# ESP32.net
KiCad netlist of a schematic drawn in Altium Designer
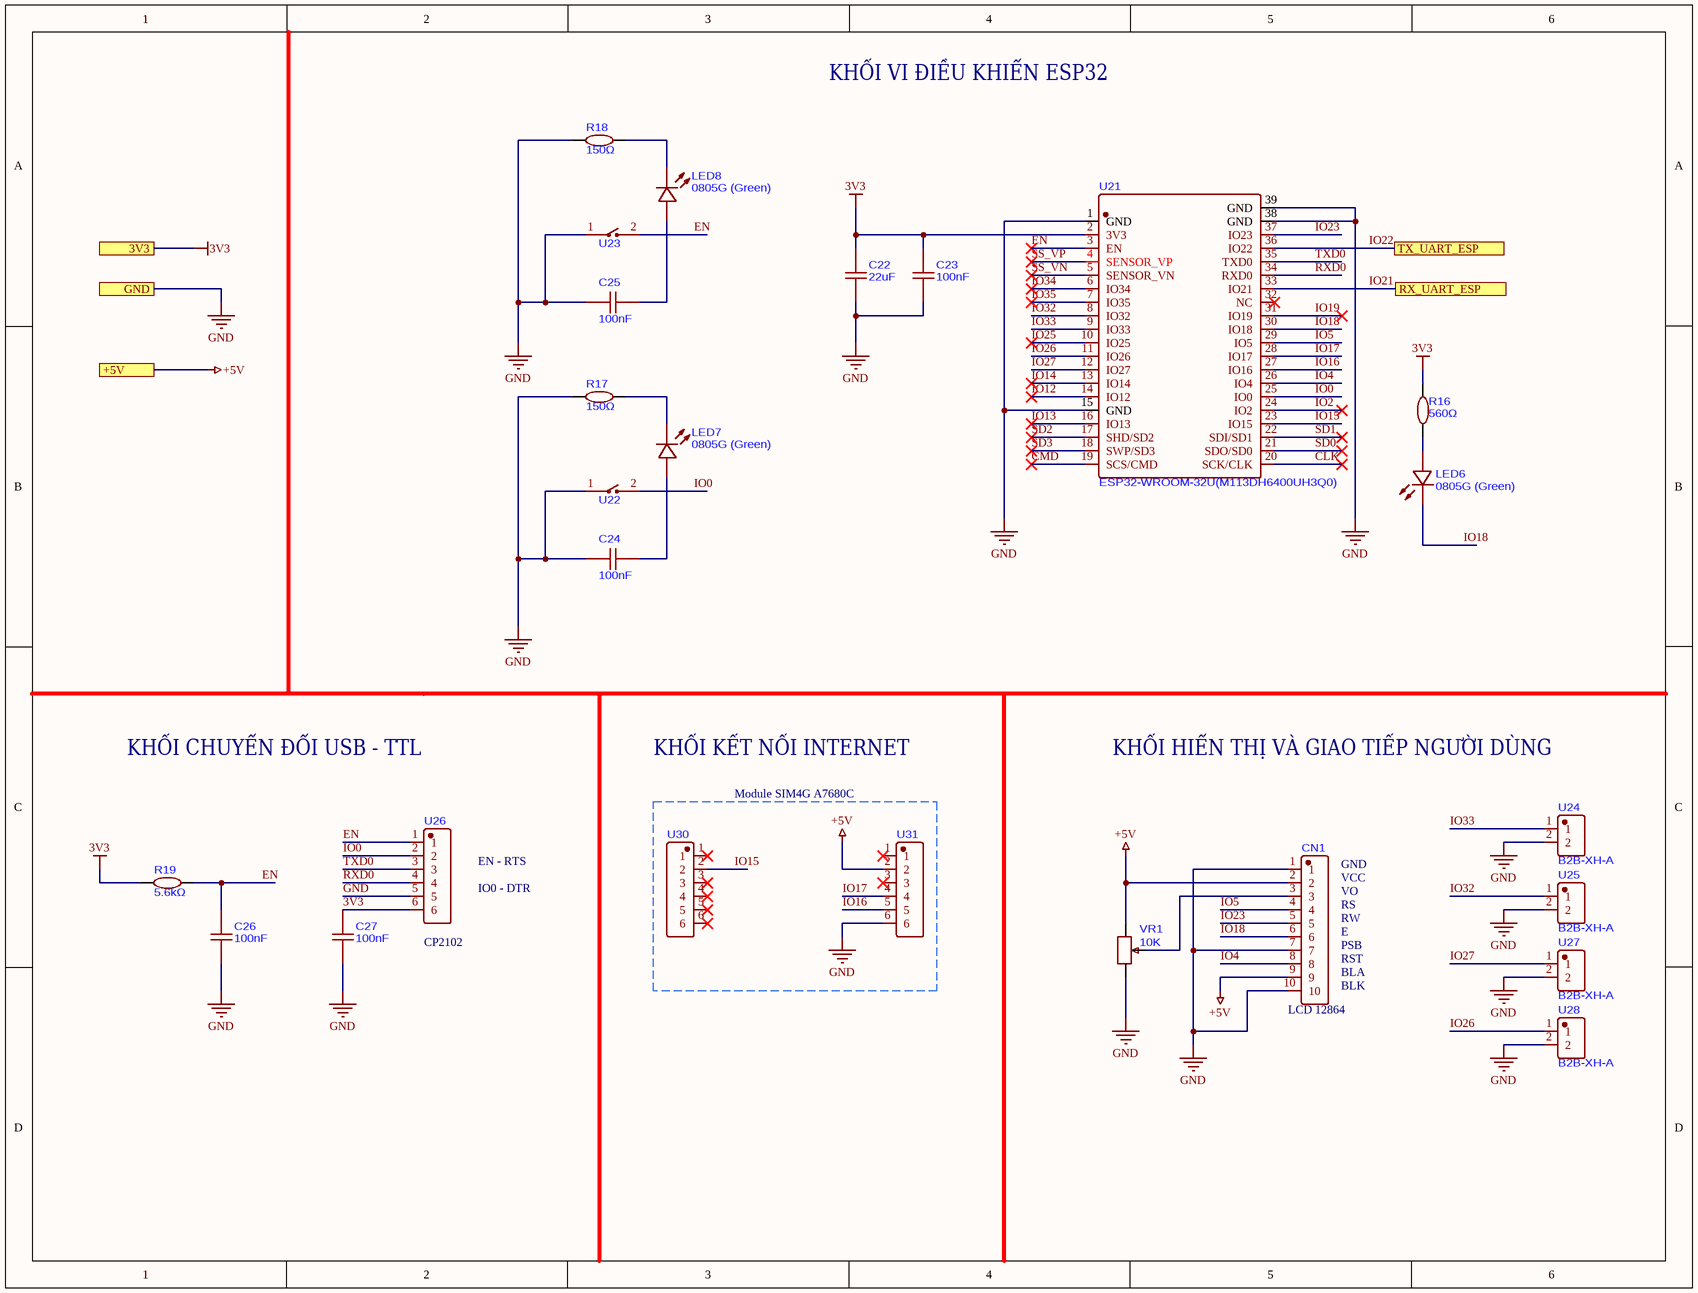
[diagram p0: ESP32.SchDoc]

(export (version "E")
  (design (tool "Eeschema 10.0.6"))
  (components
    (comp (ref "C22")
      (value "22uF")
      (footprint "C0805")
      (libsource (lib "CAP 0.1uF") (part "CC0805KRX7R9BB104"))
    )
    (comp (ref "C23")
      (value "100nF")
      (footprint "C0805")
      (libsource (lib "CAP 0.1uF") (part "CC0805KRX7R9BB104"))
    )
    (comp (ref "C24")
      (value "100nF")
      (footprint "C0805")
      (libsource (lib "CAP 0.1uF") (part "CC0805KRX7R9BB104"))
    )
    (comp (ref "C25")
      (value "100nF")
      (footprint "C0805")
      (libsource (lib "CAP 0.1uF") (part "CC0805KRX7R9BB104"))
    )
    (comp (ref "C26")
      (value "100nF")
      (footprint "C0805")
      (libsource (lib "CAP 0.1uF") (part "CC0805KRX7R9BB104"))
    )
    (comp (ref "C27")
      (value "100nF")
      (footprint "C0805")
      (libsource (lib "CAP 0.1uF") (part "CC0805KRX7R9BB104"))
    )
    (comp (ref "CN1")
      (value "ZX-XH2.54-10PZZ-GW")
      (footprint "CONN-TH_10P-P2.50_ZX-XH2.54-10PZZ-GW")
      (libsource (lib "header 1p") (part "ZX-XH2.54-10PZZ-GW"))
    )
    (comp (ref "LED6")
      (value "0805G (Green)")
      (footprint "LED0805-R-RD")
      (libsource (lib "C2297") (part "0805G (Green)"))
    )
    (comp (ref "LED7")
      (value "0805G (Green)")
      (footprint "LED0805-R-RD")
      (libsource (lib "C2297") (part "0805G (Green)"))
    )
    (comp (ref "LED8")
      (value "0805G (Green)")
      (footprint "LED0805-R-RD")
      (libsource (lib "C2297") (part "0805G (Green)"))
    )
    (comp (ref "R16") (value "560Ω") (footprint "R0805") (libsource (lib "C27834") (part "0805W8F5101T5E")))
    (comp (ref "R17")
      (value "150Ω")
      (footprint "R0805")
      (libsource (lib "RES 330") (part "RC0805FR-07330RL"))
    )
    (comp (ref "R18")
      (value "150Ω")
      (footprint "R0805")
      (libsource (lib "RES 330") (part "RC0805FR-07330RL"))
    )
    (comp (ref "R19")
      (value "5.6kΩ")
      (footprint "R0805")
      (libsource (lib "res 5.6k") (part "RC0805FR-075K6L"))
    )
    (comp (ref "U21")
      (value "ESP32-WROOM-32U(M113DH6400UH3Q0)")
      (footprint "WIFI-SMD_ESP32-WROOM-32UE-A")
      (libsource (lib "ESP32_sch") (part "ESP32-WROOM-32U(M113DH6400UH3Q0)"))
    )
    (comp (ref "U22")
      (value "轻触按键 3X6X2.5MM")
      (footprint "SW-SMD_L6.1-W3.7-LS8.0")
      (libsource (lib "button") (part "轻触按键 3X6X2.5MM"))
    )
    (comp (ref "U23")
      (value "轻触按键 3X6X2.5MM")
      (footprint "SW-SMD_L6.1-W3.7-LS8.0")
      (libsource (lib "button") (part "轻触按键 3X6X2.5MM"))
    )
    (comp (ref "U24")
      (value "B2B-XH-A")
      (footprint "CONN-TH_XH-2A")
      (libsource (lib "header 3x2") (part "B2B-XH-A"))
    )
    (comp (ref "U25")
      (value "B2B-XH-A")
      (footprint "CONN-TH_XH-2A")
      (libsource (lib "header 3x2") (part "B2B-XH-A"))
    )
    (comp (ref "U26")
      (value "HB-PH3-25416PB2GOP")
      (footprint "HDR-TH_6P-P2.54-V-M")
      (libsource (lib "header 1p") (part "HB-PH3-25416PB2GOP"))
    )
    (comp (ref "U27")
      (value "B2B-XH-A")
      (footprint "CONN-TH_XH-2A")
      (libsource (lib "header 3x2") (part "B2B-XH-A"))
    )
    (comp (ref "U28")
      (value "B2B-XH-A")
      (footprint "CONN-TH_XH-2A")
      (libsource (lib "header 3x2") (part "B2B-XH-A"))
    )
    (comp (ref "U30")
      (value "HB-PH3-25416PB2GOP")
      (footprint "HDR-TH_6P-P2.54-V-M")
      (libsource (lib "header 1p") (part "HB-PH3-25416PB2GOP"))
    )
    (comp (ref "U31")
      (value "HB-PH3-25416PB2GOP")
      (footprint "HDR-TH_6P-P2.54-V-M")
      (libsource (lib "header 1p") (part "HB-PH3-25416PB2GOP"))
    )
    (comp (ref "VR1")
      (value "10K")
      (footprint "RES-ADJ-TH_3P-L9.5-W9.5-P2.50-3386P-1-103_C48601064")
      (libsource (lib "VR 10K") (part "3386P-1-103_C48601064"))
    )
  )
  (nets
    (net (code "1") (name "+5V") (class "Default")
      (node (ref "CN1") (pin "2") (pinfunction "2_2") (pintype "passive"))
      (node (ref "CN1") (pin "9") (pinfunction "9_9") (pintype "passive"))
      (node (ref "U31") (pin "2") (pinfunction "2_2") (pintype "passive"))
      (node (ref "VR1") (pin "1") (pinfunction "1_1") (pintype "passive"))
    )
    (net (code "2") (name "/CLK") (class "Default")
      (node (ref "U21") (pin "20") (pinfunction "SCK/CLK_20") (pintype "passive+no_connect"))
    )
    (net (code "3") (name "/CMD") (class "Default")
      (node (ref "U21") (pin "19") (pinfunction "SCS/CMD_19") (pintype "passive+no_connect"))
    )
    (net (code "4") (name "/EN") (class "Default")
      (node (ref "C26") (pin "2") (pinfunction "2_2") (pintype "passive"))
      (node (ref "R19") (pin "2") (pinfunction "2_2") (pintype "passive"))
      (node (ref "U21") (pin "3") (pinfunction "EN_3") (pintype "passive"))
      (node (ref "U23") (pin "2") (pinfunction "2_2") (pintype "passive"))
      (node (ref "U26") (pin "1") (pinfunction "1_1") (pintype "passive"))
    )
    (net (code "5") (name "/IO0") (class "Default")
      (node (ref "U21") (pin "25") (pinfunction "IO0_25") (pintype "passive"))
      (node (ref "U22") (pin "2") (pinfunction "2_2") (pintype "passive"))
      (node (ref "U26") (pin "2") (pinfunction "2_2") (pintype "passive"))
    )
    (net (code "6") (name "/IO2") (class "Default")
      (node (ref "U21") (pin "24") (pinfunction "IO2_24") (pintype "passive+no_connect"))
    )
    (net (code "7") (name "/IO4") (class "Default")
      (node (ref "CN1") (pin "8") (pinfunction "8_8") (pintype "passive"))
      (node (ref "U21") (pin "26") (pinfunction "IO4_26") (pintype "passive"))
    )
    (net (code "8") (name "/IO5") (class "Default")
      (node (ref "CN1") (pin "4") (pinfunction "4_4") (pintype "passive"))
      (node (ref "U21") (pin "29") (pinfunction "IO5_29") (pintype "passive"))
    )
    (net (code "9") (name "/IO12") (class "Default")
      (node (ref "U21") (pin "14") (pinfunction "IO12_14") (pintype "passive+no_connect"))
    )
    (net (code "10") (name "/IO13") (class "Default")
      (node (ref "U21") (pin "16") (pinfunction "IO13_16") (pintype "passive+no_connect"))
    )
    (net (code "11") (name "/IO14") (class "Default")
      (node (ref "U21") (pin "13") (pinfunction "IO14_13") (pintype "passive+no_connect"))
    )
    (net (code "12") (name "/IO15") (class "Default")
      (node (ref "U21") (pin "23") (pinfunction "IO15_23") (pintype "passive"))
      (node (ref "U30") (pin "2") (pinfunction "2_2") (pintype "passive"))
    )
    (net (code "13") (name "/IO16") (class "Default")
      (node (ref "U21") (pin "27") (pinfunction "IO16_27") (pintype "passive"))
      (node (ref "U31") (pin "5") (pinfunction "5_5") (pintype "passive"))
    )
    (net (code "14") (name "/IO17") (class "Default")
      (node (ref "U21") (pin "28") (pinfunction "IO17_28") (pintype "passive"))
      (node (ref "U31") (pin "4") (pinfunction "4_4") (pintype "passive"))
    )
    (net (code "15") (name "/IO18") (class "Default")
      (node (ref "CN1") (pin "6") (pinfunction "6_6") (pintype "passive"))
      (node (ref "LED6") (pin "2") (pinfunction "K_2") (pintype "passive"))
      (node (ref "U21") (pin "30") (pinfunction "IO18_30") (pintype "passive"))
    )
    (net (code "16") (name "/IO19") (class "Default")
      (node (ref "U21") (pin "31") (pinfunction "IO19_31") (pintype "passive+no_connect"))
    )
    (net (code "17") (name "/IO21") (class "Default")
      (node (ref "U21") (pin "33") (pinfunction "IO21_33") (pintype "passive"))
    )
    (net (code "18") (name "/IO22") (class "Default")
      (node (ref "U21") (pin "36") (pinfunction "IO22_36") (pintype "passive"))
    )
    (net (code "19") (name "/IO23") (class "Default")
      (node (ref "CN1") (pin "5") (pinfunction "5_5") (pintype "passive"))
      (node (ref "U21") (pin "37") (pinfunction "IO23_37") (pintype "passive"))
    )
    (net (code "20") (name "/IO25") (class "Default")
      (node (ref "U21") (pin "10") (pinfunction "IO25_10") (pintype "passive+no_connect"))
    )
    (net (code "21") (name "/IO26") (class "Default")
      (node (ref "U21") (pin "11") (pinfunction "IO26_11") (pintype "passive"))
      (node (ref "U28") (pin "1") (pinfunction "1_1") (pintype "passive"))
    )
    (net (code "22") (name "/IO27") (class "Default")
      (node (ref "U21") (pin "12") (pinfunction "IO27_12") (pintype "passive"))
      (node (ref "U27") (pin "1") (pinfunction "1_1") (pintype "passive"))
    )
    (net (code "23") (name "/IO32") (class "Default")
      (node (ref "U21") (pin "8") (pinfunction "IO32_8") (pintype "passive"))
      (node (ref "U25") (pin "1") (pinfunction "1_1") (pintype "passive"))
    )
    (net (code "24") (name "/IO33") (class "Default")
      (node (ref "U21") (pin "9") (pinfunction "IO33_9") (pintype "passive"))
      (node (ref "U24") (pin "1") (pinfunction "1_1") (pintype "passive"))
    )
    (net (code "25") (name "/IO34") (class "Default")
      (node (ref "U21") (pin "6") (pinfunction "IO34_6") (pintype "passive+no_connect"))
    )
    (net (code "26") (name "/IO35") (class "Default")
      (node (ref "U21") (pin "7") (pinfunction "IO35_7") (pintype "passive+no_connect"))
    )
    (net (code "27") (name "/RXD0") (class "Default")
      (node (ref "U21") (pin "34") (pinfunction "RXD0_34") (pintype "passive"))
      (node (ref "U26") (pin "4") (pinfunction "4_4") (pintype "passive"))
    )
    (net (code "28") (name "/SD0") (class "Default")
      (node (ref "U21") (pin "21") (pinfunction "SDO/SD0_21") (pintype "passive+no_connect"))
    )
    (net (code "29") (name "/SD1") (class "Default")
      (node (ref "U21") (pin "22") (pinfunction "SDI/SD1_22") (pintype "passive+no_connect"))
    )
    (net (code "30") (name "/SD2") (class "Default")
      (node (ref "U21") (pin "17") (pinfunction "SHD/SD2_17") (pintype "passive+no_connect"))
    )
    (net (code "31") (name "/SD3") (class "Default")
      (node (ref "U21") (pin "18") (pinfunction "SWP/SD3_18") (pintype "passive+no_connect"))
    )
    (net (code "32") (name "/SS_VN") (class "Default")
      (node (ref "U21") (pin "5") (pinfunction "SENSOR_VN_5") (pintype "passive+no_connect"))
    )
    (net (code "33") (name "/SS_VP") (class "Default")
      (node (ref "U21") (pin "4") (pinfunction "SENSOR_VP_4") (pintype "passive+no_connect"))
    )
    (net (code "34") (name "/TXD0") (class "Default")
      (node (ref "U21") (pin "35") (pinfunction "TXD0_35") (pintype "passive"))
      (node (ref "U26") (pin "3") (pinfunction "3_3") (pintype "passive"))
    )
    (net (code "35") (name "3V3") (class "Default")
      (node (ref "C22") (pin "2") (pinfunction "2_2") (pintype "passive"))
      (node (ref "C23") (pin "2") (pinfunction "2_2") (pintype "passive"))
      (node (ref "C27") (pin "2") (pinfunction "2_2") (pintype "passive"))
      (node (ref "R16") (pin "2") (pinfunction "2_2") (pintype "passive"))
      (node (ref "R19") (pin "1") (pinfunction "1_1") (pintype "passive"))
      (node (ref "U21") (pin "2") (pinfunction "3V3_2") (pintype "passive"))
      (node (ref "U26") (pin "6") (pinfunction "6_6") (pintype "passive"))
    )
    (net (code "36") (name "GND") (class "Default")
      (node (ref "C22") (pin "1") (pinfunction "1_1") (pintype "passive"))
      (node (ref "C23") (pin "1") (pinfunction "1_1") (pintype "passive"))
      (node (ref "C24") (pin "2") (pinfunction "2_2") (pintype "passive"))
      (node (ref "C25") (pin "2") (pinfunction "2_2") (pintype "passive"))
      (node (ref "C26") (pin "1") (pinfunction "1_1") (pintype "passive"))
      (node (ref "C27") (pin "1") (pinfunction "1_1") (pintype "passive"))
      (node (ref "CN1") (pin "1") (pinfunction "1_1") (pintype "passive"))
      (node (ref "CN1") (pin "10") (pinfunction "10_10") (pintype "passive"))
      (node (ref "CN1") (pin "7") (pinfunction "7_7") (pintype "passive"))
      (node (ref "R17") (pin "2") (pinfunction "2_2") (pintype "passive"))
      (node (ref "R18") (pin "2") (pinfunction "2_2") (pintype "passive"))
      (node (ref "U21") (pin "1") (pinfunction "GND_1") (pintype "passive"))
      (node (ref "U21") (pin "15") (pinfunction "GND_15") (pintype "passive"))
      (node (ref "U21") (pin "38") (pinfunction "GND_38") (pintype "passive"))
      (node (ref "U21") (pin "39") (pinfunction "GND_39") (pintype "passive"))
      (node (ref "U22") (pin "1") (pinfunction "1_1") (pintype "passive"))
      (node (ref "U23") (pin "1") (pinfunction "1_1") (pintype "passive"))
      (node (ref "U24") (pin "2") (pinfunction "2_2") (pintype "passive"))
      (node (ref "U25") (pin "2") (pinfunction "2_2") (pintype "passive"))
      (node (ref "U26") (pin "5") (pinfunction "5_5") (pintype "passive"))
      (node (ref "U27") (pin "2") (pinfunction "2_2") (pintype "passive"))
      (node (ref "U28") (pin "2") (pinfunction "2_2") (pintype "passive"))
      (node (ref "U31") (pin "6") (pinfunction "6_6") (pintype "passive"))
      (node (ref "VR1") (pin "3") (pinfunction "3_3") (pintype "passive"))
    )
    (net (code "37") (name "Net-(CN1-Pad3)") (class "Default")
      (node (ref "CN1") (pin "3") (pinfunction "3_3") (pintype "passive"))
      (node (ref "VR1") (pin "2") (pinfunction "2_2") (pintype "passive"))
    )
    (net (code "38") (name "Net-(LED6-A)") (class "Default")
      (node (ref "LED6") (pin "1") (pinfunction "A_1") (pintype "passive"))
      (node (ref "R16") (pin "1") (pinfunction "1_1") (pintype "passive"))
    )
    (net (code "39") (name "Net-(LED7-A)") (class "Default")
      (node (ref "C24") (pin "1") (pinfunction "1_1") (pintype "passive"))
      (node (ref "LED7") (pin "1") (pinfunction "A_1") (pintype "passive"))
    )
    (net (code "40") (name "Net-(LED7-K)") (class "Default")
      (node (ref "LED7") (pin "2") (pinfunction "K_2") (pintype "passive"))
      (node (ref "R17") (pin "1") (pinfunction "1_1") (pintype "passive"))
    )
    (net (code "41") (name "Net-(LED8-A)") (class "Default")
      (node (ref "C25") (pin "1") (pinfunction "1_1") (pintype "passive"))
      (node (ref "LED8") (pin "1") (pinfunction "A_1") (pintype "passive"))
    )
    (net (code "42") (name "Net-(LED8-K)") (class "Default")
      (node (ref "LED8") (pin "2") (pinfunction "K_2") (pintype "passive"))
      (node (ref "R18") (pin "1") (pinfunction "1_1") (pintype "passive"))
    )
    (net (code "43") (name "unconnected-(U21-NC-Pad32)") (class "Default")
      (node (ref "U21") (pin "32") (pinfunction "NC_32") (pintype "passive+no_connect"))
    )
    (net (code "44") (name "unconnected-(U30-Pad1)") (class "Default")
      (node (ref "U30") (pin "1") (pinfunction "1_1") (pintype "passive+no_connect"))
    )
    (net (code "45") (name "unconnected-(U30-Pad3)") (class "Default")
      (node (ref "U30") (pin "3") (pinfunction "3_3") (pintype "passive+no_connect"))
    )
    (net (code "46") (name "unconnected-(U30-Pad4)") (class "Default")
      (node (ref "U30") (pin "4") (pinfunction "4_4") (pintype "passive+no_connect"))
    )
    (net (code "47") (name "unconnected-(U30-Pad5)") (class "Default")
      (node (ref "U30") (pin "5") (pinfunction "5_5") (pintype "passive+no_connect"))
    )
    (net (code "48") (name "unconnected-(U30-Pad6)") (class "Default")
      (node (ref "U30") (pin "6") (pinfunction "6_6") (pintype "passive+no_connect"))
    )
    (net (code "49") (name "unconnected-(U31-Pad1)") (class "Default")
      (node (ref "U31") (pin "1") (pinfunction "1_1") (pintype "passive+no_connect"))
    )
    (net (code "50") (name "unconnected-(U31-Pad3)") (class "Default")
      (node (ref "U31") (pin "3") (pinfunction "3_3") (pintype "passive+no_connect"))
    )
  )
)
